# GuitArduino_Schematic_EasyEDA.net
KiCad netlist of a schematic drawn in EasyEDA
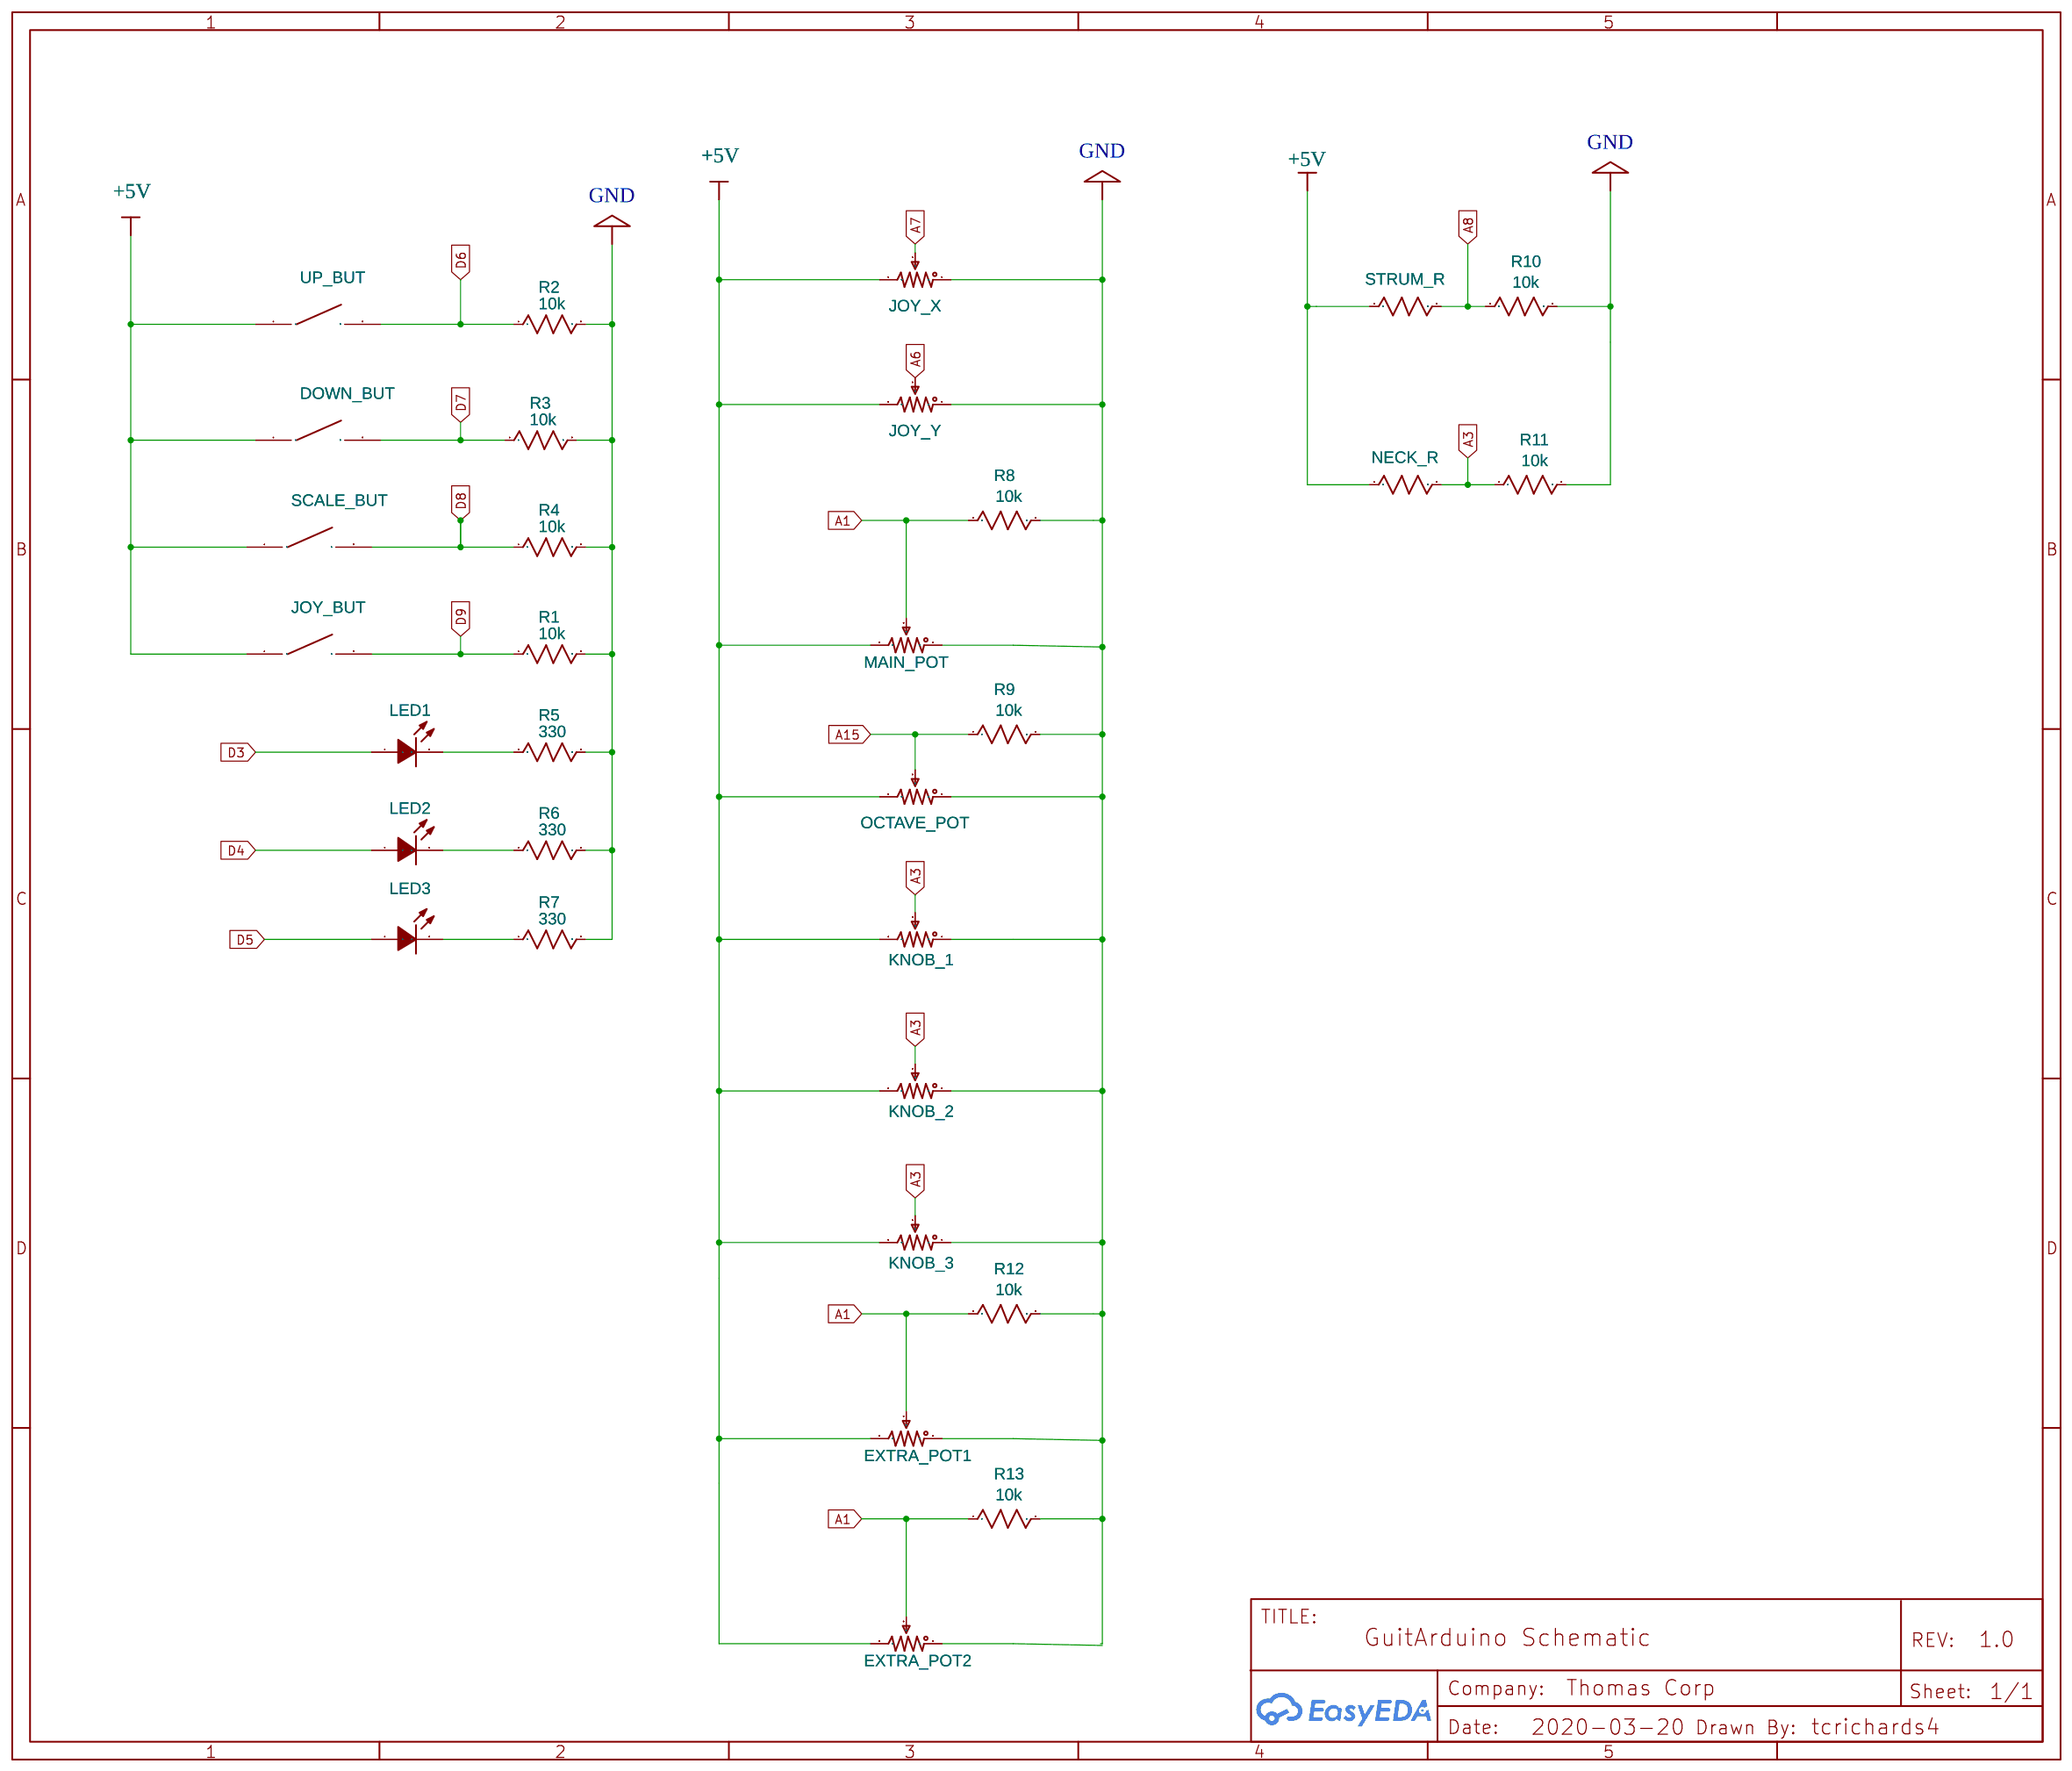
[diagram p0: schematic sheet]

(export (version "E")
  (design (tool "Eeschema 10.0.6"))
  (components
    (comp (ref "DOWN_BUT")
      (value "EVQ22705R")
      (fields (field (name "BOM_Supplier Part") "C79156"))
      (libsource (lib "") (part "EVQ22705R_2"))
    )
    (comp (ref "EXTRA_POT1")
      (value "100")
      (fields
        (field (name "BOM_Manufacturer Part") "3386P-1-101LF")
        (field (name "BOM_Supplier Part") "C125022")
      )
      (libsource (lib "") (part "3386P-1-101LF_US_1"))
    )
    (comp (ref "EXTRA_POT2")
      (value "100")
      (fields
        (field (name "BOM_Manufacturer Part") "3386P-1-101LF")
        (field (name "BOM_Supplier Part") "C125022")
      )
      (libsource (lib "") (part "3386P-1-101LF_US_1"))
    )
    (comp (ref "JOY_BUT")
      (value "EVQ22705R")
      (fields (field (name "BOM_Supplier Part") "C79156"))
      (libsource (lib "") (part "EVQ22705R_1"))
    )
    (comp (ref "JOY_X")
      (value "100")
      (fields
        (field (name "BOM_Manufacturer Part") "3386P-1-101LF")
        (field (name "BOM_Supplier Part") "C125022")
      )
      (libsource (lib "") (part "3386P-1-101LF_US_2"))
    )
    (comp (ref "JOY_Y")
      (value "100")
      (fields
        (field (name "BOM_Manufacturer Part") "3386P-1-101LF")
        (field (name "BOM_Supplier Part") "C125022")
      )
      (libsource (lib "") (part "3386P-1-101LF_US_4"))
    )
    (comp (ref "KNOB_1")
      (value "100")
      (fields
        (field (name "BOM_Manufacturer Part") "3386P-1-101LF")
        (field (name "BOM_Supplier Part") "C125022")
      )
      (libsource (lib "") (part "3386P-1-101LF_US_3"))
    )
    (comp (ref "KNOB_2")
      (value "100")
      (fields
        (field (name "BOM_Manufacturer Part") "3386P-1-101LF")
        (field (name "BOM_Supplier Part") "C125022")
      )
      (libsource (lib "") (part "3386P-1-101LF_US_3"))
    )
    (comp (ref "KNOB_3")
      (value "100")
      (fields
        (field (name "BOM_Manufacturer Part") "3386P-1-101LF")
        (field (name "BOM_Supplier Part") "C125022")
      )
      (libsource (lib "") (part "3386P-1-101LF_US_3"))
    )
    (comp (ref "LED1")
      (value "204-10SURD/S530-A3")
      (fields (field (name "BOM_Supplier Part") "C99772"))
      (libsource (lib "") (part "204-10SURD/S530-A3"))
    )
    (comp (ref "LED2")
      (value "204-10SURD/S530-A3")
      (fields (field (name "BOM_Supplier Part") "C99772"))
      (libsource (lib "") (part "204-10SURD/S530-A3"))
    )
    (comp (ref "LED3")
      (value "204-10SURD/S530-A3")
      (fields (field (name "BOM_Supplier Part") "C99772"))
      (libsource (lib "") (part "204-10SURD/S530-A3"))
    )
    (comp (ref "MAIN_POT")
      (value "100")
      (fields
        (field (name "BOM_Manufacturer Part") "3386P-1-101LF")
        (field (name "BOM_Supplier Part") "C125022")
      )
      (libsource (lib "") (part "3386P-1-101LF_US_5"))
    )
    (comp (ref "NECK_R") (value "1k") (libsource (lib "") (part "Res_AXIAL-0.3(1/8W)_US_1")))
    (comp (ref "OCTAVE_POT")
      (value "100")
      (fields
        (field (name "BOM_Manufacturer Part") "3386P-1-101LF")
        (field (name "BOM_Supplier Part") "C125022")
      )
      (libsource (lib "") (part "3386P-1-101LF_US"))
    )
    (comp (ref "R1") (value "10k") (libsource (lib "") (part "Res_AXIAL-0.3(1/8W)_US")))
    (comp (ref "R2") (value "10k") (libsource (lib "") (part "Res_AXIAL-0.3(1/8W)_US")))
    (comp (ref "R3") (value "10k") (libsource (lib "") (part "Res_AXIAL-0.3(1/8W)_US")))
    (comp (ref "R4") (value "10k") (libsource (lib "") (part "Res_AXIAL-0.3(1/8W)_US")))
    (comp (ref "R5") (value "330") (libsource (lib "") (part "Res_AXIAL-0.3(1/8W)_US")))
    (comp (ref "R6") (value "330") (libsource (lib "") (part "Res_AXIAL-0.3(1/8W)_US")))
    (comp (ref "R7") (value "330") (libsource (lib "") (part "Res_AXIAL-0.3(1/8W)_US")))
    (comp (ref "R8") (value "10k") (libsource (lib "") (part "Res_AXIAL-0.3(1/8W)_US")))
    (comp (ref "R9") (value "10k") (libsource (lib "") (part "Res_AXIAL-0.3(1/8W)_US")))
    (comp (ref "R10") (value "10k") (libsource (lib "") (part "Res_AXIAL-0.3(1/8W)_US")))
    (comp (ref "R11") (value "10k") (libsource (lib "") (part "Res_AXIAL-0.3(1/8W)_US")))
    (comp (ref "R12") (value "10k") (libsource (lib "") (part "Res_AXIAL-0.3(1/8W)_US")))
    (comp (ref "R13") (value "10k") (libsource (lib "") (part "Res_AXIAL-0.3(1/8W)_US")))
    (comp (ref "SCALE_BUT")
      (value "EVQ22705R")
      (fields (field (name "BOM_Supplier Part") "C79156"))
      (libsource (lib "") (part "EVQ22705R_3"))
    )
    (comp (ref "STRUM_R") (value "1k") (libsource (lib "") (part "Res_AXIAL-0.3(1/8W)_US_2")))
    (comp (ref "UP_BUT")
      (value "EVQ22705R")
      (fields (field (name "BOM_Supplier Part") "C79156"))
      (libsource (lib "") (part "EVQ22705R"))
    )
  )
  (nets
    (net (code "1") (name "+5V") (class "Default")
      (node (ref "DOWN_BUT") (pin "1") (pinfunction "1_1") (pintype "input"))
      (node (ref "EXTRA_POT1") (pin "3") (pinfunction "3_3") (pintype "unspecified"))
      (node (ref "EXTRA_POT2") (pin "3") (pinfunction "3_3") (pintype "unspecified"))
      (node (ref "JOY_BUT") (pin "1") (pinfunction "1_1") (pintype "input"))
      (node (ref "JOY_X") (pin "3") (pinfunction "3_3") (pintype "unspecified"))
      (node (ref "JOY_Y") (pin "3") (pinfunction "3_3") (pintype "unspecified"))
      (node (ref "KNOB_1") (pin "3") (pinfunction "3_3") (pintype "unspecified"))
      (node (ref "KNOB_2") (pin "3") (pinfunction "3_3") (pintype "unspecified"))
      (node (ref "KNOB_3") (pin "3") (pinfunction "3_3") (pintype "unspecified"))
      (node (ref "MAIN_POT") (pin "3") (pinfunction "3_3") (pintype "unspecified"))
      (node (ref "NECK_R") (pin "1") (pinfunction "1_1") (pintype "unspecified"))
      (node (ref "OCTAVE_POT") (pin "3") (pinfunction "3_3") (pintype "unspecified"))
      (node (ref "SCALE_BUT") (pin "1") (pinfunction "1_1") (pintype "input"))
      (node (ref "STRUM_R") (pin "1") (pinfunction "1_1") (pintype "unspecified"))
      (node (ref "UP_BUT") (pin "1") (pinfunction "1_1") (pintype "input"))
    )
    (net (code "2") (name "A1") (class "Default")
      (node (ref "EXTRA_POT1") (pin "2") (pinfunction "2_2") (pintype "unspecified"))
      (node (ref "EXTRA_POT2") (pin "2") (pinfunction "2_2") (pintype "unspecified"))
      (node (ref "MAIN_POT") (pin "2") (pinfunction "2_2") (pintype "unspecified"))
      (node (ref "R12") (pin "1") (pinfunction "1_1") (pintype "unspecified"))
      (node (ref "R13") (pin "1") (pinfunction "1_1") (pintype "unspecified"))
      (node (ref "R8") (pin "1") (pinfunction "1_1") (pintype "unspecified"))
    )
    (net (code "3") (name "A3") (class "Default")
      (node (ref "KNOB_1") (pin "2") (pinfunction "2_2") (pintype "unspecified"))
      (node (ref "KNOB_2") (pin "2") (pinfunction "2_2") (pintype "unspecified"))
      (node (ref "KNOB_3") (pin "2") (pinfunction "2_2") (pintype "unspecified"))
      (node (ref "NECK_R") (pin "2") (pinfunction "2_2") (pintype "unspecified"))
      (node (ref "R11") (pin "1") (pinfunction "1_1") (pintype "unspecified"))
    )
    (net (code "4") (name "A6") (class "Default")
      (node (ref "JOY_Y") (pin "2") (pinfunction "2_2") (pintype "unspecified"))
    )
    (net (code "5") (name "A7") (class "Default")
      (node (ref "JOY_X") (pin "2") (pinfunction "2_2") (pintype "unspecified"))
    )
    (net (code "6") (name "A8") (class "Default")
      (node (ref "R10") (pin "1") (pinfunction "1_1") (pintype "unspecified"))
      (node (ref "STRUM_R") (pin "2") (pinfunction "2_2") (pintype "unspecified"))
    )
    (net (code "7") (name "A15") (class "Default")
      (node (ref "OCTAVE_POT") (pin "2") (pinfunction "2_2") (pintype "unspecified"))
      (node (ref "R9") (pin "1") (pinfunction "1_1") (pintype "unspecified"))
    )
    (net (code "8") (name "D3") (class "Default")
      (node (ref "LED1") (pin "1") (pinfunction "A_1") (pintype "unspecified"))
    )
    (net (code "9") (name "D4") (class "Default")
      (node (ref "LED2") (pin "1") (pinfunction "A_1") (pintype "unspecified"))
    )
    (net (code "10") (name "D5") (class "Default")
      (node (ref "LED3") (pin "1") (pinfunction "A_1") (pintype "unspecified"))
    )
    (net (code "11") (name "D6") (class "Default")
      (node (ref "R2") (pin "1") (pinfunction "1_1") (pintype "unspecified"))
      (node (ref "UP_BUT") (pin "2") (pinfunction "2_2") (pintype "input"))
    )
    (net (code "12") (name "D7") (class "Default")
      (node (ref "DOWN_BUT") (pin "2") (pinfunction "2_2") (pintype "input"))
      (node (ref "R3") (pin "1") (pinfunction "1_1") (pintype "unspecified"))
    )
    (net (code "13") (name "D8") (class "Default")
      (node (ref "R4") (pin "1") (pinfunction "1_1") (pintype "unspecified"))
      (node (ref "SCALE_BUT") (pin "2") (pinfunction "2_2") (pintype "input"))
    )
    (net (code "14") (name "D9") (class "Default")
      (node (ref "JOY_BUT") (pin "2") (pinfunction "2_2") (pintype "input"))
      (node (ref "R1") (pin "1") (pinfunction "1_1") (pintype "unspecified"))
    )
    (net (code "15") (name "GND") (class "Default")
      (node (ref "EXTRA_POT1") (pin "1") (pinfunction "1_1") (pintype "unspecified"))
      (node (ref "JOY_X") (pin "1") (pinfunction "1_1") (pintype "unspecified"))
      (node (ref "JOY_Y") (pin "1") (pinfunction "1_1") (pintype "unspecified"))
      (node (ref "KNOB_1") (pin "1") (pinfunction "1_1") (pintype "unspecified"))
      (node (ref "KNOB_2") (pin "1") (pinfunction "1_1") (pintype "unspecified"))
      (node (ref "KNOB_3") (pin "1") (pinfunction "1_1") (pintype "unspecified"))
      (node (ref "MAIN_POT") (pin "1") (pinfunction "1_1") (pintype "unspecified"))
      (node (ref "OCTAVE_POT") (pin "1") (pinfunction "1_1") (pintype "unspecified"))
      (node (ref "R1") (pin "2") (pinfunction "2_2") (pintype "unspecified"))
      (node (ref "R10") (pin "2") (pinfunction "2_2") (pintype "unspecified"))
      (node (ref "R11") (pin "2") (pinfunction "2_2") (pintype "unspecified"))
      (node (ref "R12") (pin "2") (pinfunction "2_2") (pintype "unspecified"))
      (node (ref "R13") (pin "2") (pinfunction "2_2") (pintype "unspecified"))
      (node (ref "R2") (pin "2") (pinfunction "2_2") (pintype "unspecified"))
      (node (ref "R3") (pin "2") (pinfunction "2_2") (pintype "unspecified"))
      (node (ref "R4") (pin "2") (pinfunction "2_2") (pintype "unspecified"))
      (node (ref "R5") (pin "2") (pinfunction "2_2") (pintype "unspecified"))
      (node (ref "R6") (pin "2") (pinfunction "2_2") (pintype "unspecified"))
      (node (ref "R7") (pin "2") (pinfunction "2_2") (pintype "unspecified"))
      (node (ref "R8") (pin "2") (pinfunction "2_2") (pintype "unspecified"))
      (node (ref "R9") (pin "2") (pinfunction "2_2") (pintype "unspecified"))
    )
    (net (code "16") (name "Net-(LED1-K)") (class "Default")
      (node (ref "LED1") (pin "2") (pinfunction "K_2") (pintype "unspecified"))
      (node (ref "R5") (pin "1") (pinfunction "1_1") (pintype "unspecified"))
    )
    (net (code "17") (name "Net-(LED2-K)") (class "Default")
      (node (ref "LED2") (pin "2") (pinfunction "K_2") (pintype "unspecified"))
      (node (ref "R6") (pin "1") (pinfunction "1_1") (pintype "unspecified"))
    )
    (net (code "18") (name "Net-(LED3-K)") (class "Default")
      (node (ref "LED3") (pin "2") (pinfunction "K_2") (pintype "unspecified"))
      (node (ref "R7") (pin "1") (pinfunction "1_1") (pintype "unspecified"))
    )
    (net (code "19") (name "unconnected-(EXTRA_POT2-Pad1)") (class "Default")
      (node (ref "EXTRA_POT2") (pin "1") (pinfunction "1_1") (pintype "unspecified"))
    )
  )
)
